# JS7628_base_uart_v1_0.net
KiCad netlist of a schematic drawn in Altium Designer
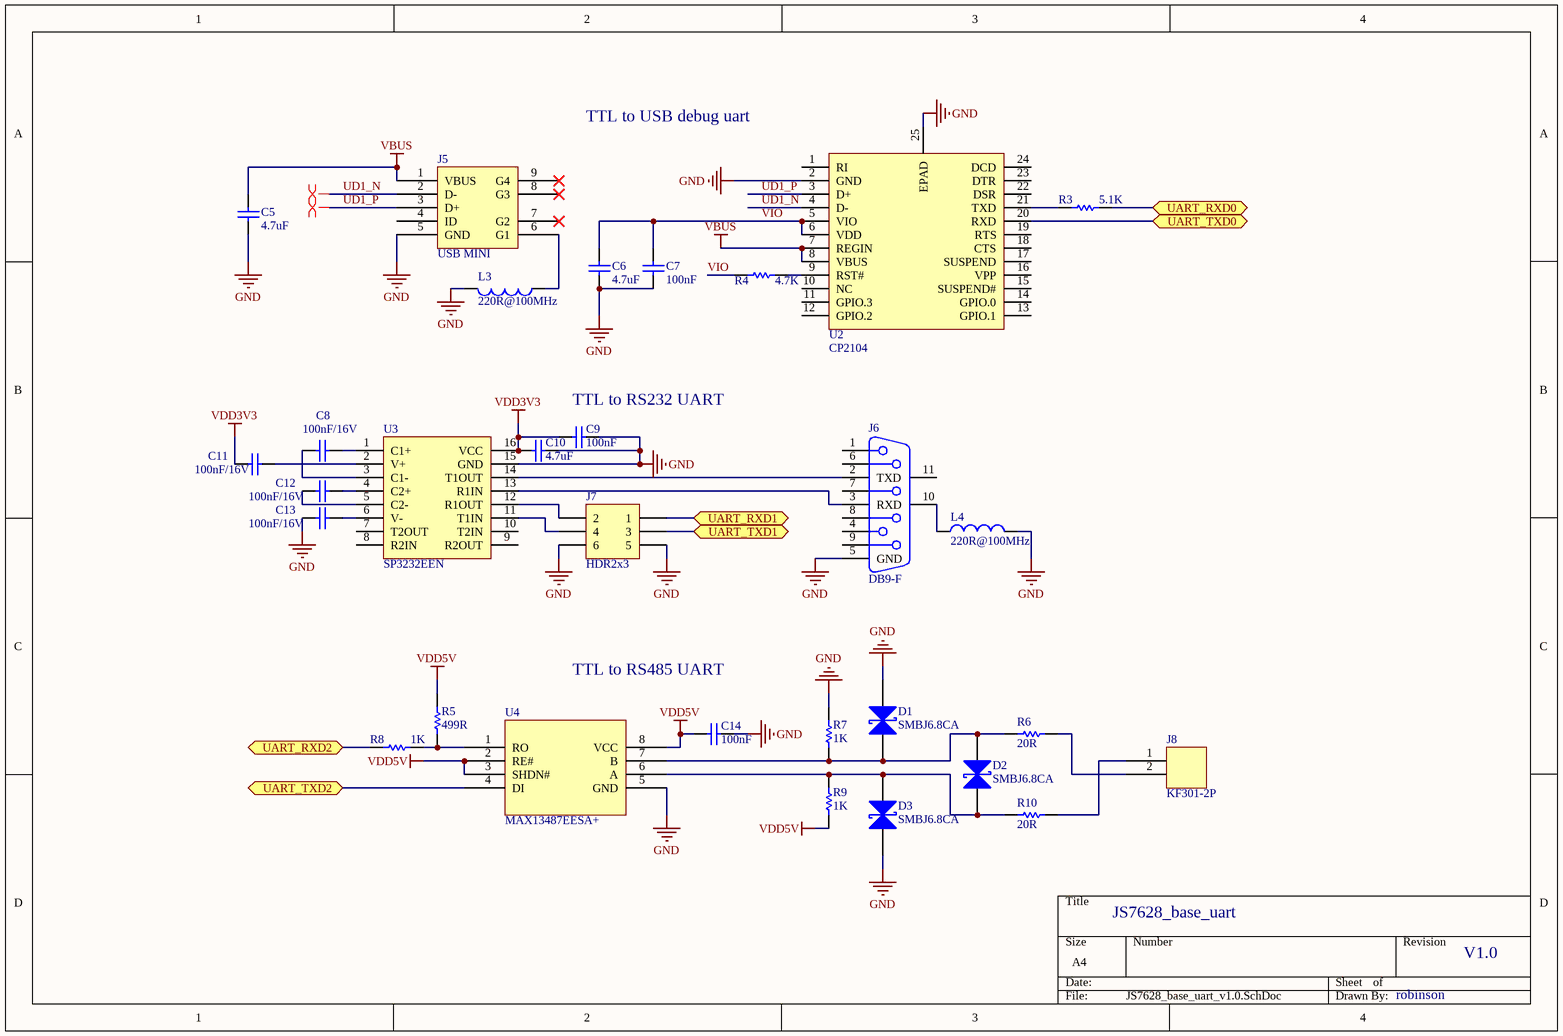
[diagram p0: JS7628_base_uart_v1.0.SchDoc]

(export (version "E")
  (design (tool "Eeschema 10.0.6"))
  (components
    (comp (ref "C5")
      (value "4.7uF")
      (footprint "0603")
      (fields (field (name "Comment") "CAP-SMT"))
      (libsource (lib "MyMiscellaneousDevice") (part "CAP-SMT"))
    )
    (comp (ref "C6")
      (value "4.7uF")
      (footprint "0603")
      (fields (field (name "Comment") "CAP-SMT"))
      (libsource (lib "MyMiscellaneousDevice") (part "CAP-SMT"))
    )
    (comp (ref "C7")
      (value "100nF")
      (footprint "0603")
      (fields (field (name "Comment") "CAP-SMT"))
      (libsource (lib "MyMiscellaneousDevice") (part "CAP-SMT"))
    )
    (comp (ref "C8")
      (value "100nF/16V")
      (footprint "0603")
      (fields (field (name "Comment") "CAP-SMT"))
      (libsource (lib "MyMiscellaneousDevice") (part "CAP-SMT"))
    )
    (comp (ref "C9")
      (value "100nF")
      (footprint "0603")
      (fields (field (name "Comment") "CAP-SMT"))
      (libsource (lib "MyMiscellaneousDevice") (part "CAP-SMT"))
    )
    (comp (ref "C10")
      (value "4.7uF")
      (footprint "0603")
      (fields (field (name "Comment") "CAP-SMT"))
      (libsource (lib "MyMiscellaneousDevice") (part "CAP-SMT"))
    )
    (comp (ref "C11")
      (value "100nF/16V")
      (footprint "0603")
      (fields (field (name "Comment") "CAP-SMT"))
      (libsource (lib "MyMiscellaneousDevice") (part "CAP-SMT"))
    )
    (comp (ref "C12")
      (value "100nF/16V")
      (footprint "0603")
      (fields (field (name "Comment") "CAP-SMT"))
      (libsource (lib "MyMiscellaneousDevice") (part "CAP-SMT"))
    )
    (comp (ref "C13")
      (value "100nF/16V")
      (footprint "0603")
      (fields (field (name "Comment") "CAP-SMT"))
      (libsource (lib "MyMiscellaneousDevice") (part "CAP-SMT"))
    )
    (comp (ref "C14")
      (value "100nF")
      (footprint "0603")
      (fields (field (name "Comment") "CAP-SMT"))
      (libsource (lib "MyMiscellaneousDevice") (part "CAP-SMT"))
    )
    (comp (ref "D1")
      (value "SMBJ6.8CA")
      (footprint "MyMiscellaneousDevice:SMB-BI")
      (libsource (lib "MyMiscellaneousDevice") (part "SMBJ6.8CA"))
    )
    (comp (ref "D2")
      (value "SMBJ6.8CA")
      (footprint "MyMiscellaneousDevice:SMB-BI")
      (libsource (lib "MyMiscellaneousDevice") (part "SMBJ6.8CA"))
    )
    (comp (ref "D3")
      (value "SMBJ6.8CA")
      (footprint "MyMiscellaneousDevice:SMB-BI")
      (libsource (lib "MyMiscellaneousDevice") (part "SMBJ6.8CA"))
    )
    (comp (ref "J5")
      (value "USB MINI")
      (footprint "USB/SM0.8-6H5")
      (libsource (lib "MyMiscellaneousConnector") (part "USB MINI"))
    )
    (comp (ref "J6")
      (value "DB9-F")
      (footprint "DB9-F-90d")
      (libsource (lib "MyMiscellaneousConnector") (part "DB9-F"))
    )
    (comp (ref "J7")
      (value "HDR2x3")
      (footprint "HDR2x3-2.54mm")
      (libsource (lib "MyMiscellaneousConnector") (part "HDR2x3"))
    )
    (comp (ref "J8")
      (value "KF301-2P")
      (footprint "KF301-2P")
      (libsource (lib "MyMiscellaneousConnector") (part "KF301-2P"))
    )
    (comp (ref "L3")
      (value "220R@100MHz")
      (footprint "0603")
      (fields (field (name "Comment") "inductor"))
      (libsource (lib "MyMiscellaneousDevice") (part "inductor"))
    )
    (comp (ref "L4")
      (value "220R@100MHz")
      (footprint "0603")
      (fields (field (name "Comment") "inductor"))
      (libsource (lib "MyMiscellaneousDevice") (part "inductor"))
    )
    (comp (ref "R3")
      (value "5.1K")
      (footprint "0603")
      (fields (field (name "Comment") "RES-SMT"))
      (libsource (lib "MyMiscellaneousDevice") (part "RES-SMT"))
    )
    (comp (ref "R4")
      (value "4.7K")
      (footprint "0603")
      (fields (field (name "Comment") "RES-SMT"))
      (libsource (lib "MyMiscellaneousDevice") (part "RES-SMT"))
    )
    (comp (ref "R5")
      (value "499R")
      (footprint "0603")
      (fields (field (name "Comment") "RES-SMT"))
      (libsource (lib "MyMiscellaneousDevice") (part "RES-SMT"))
    )
    (comp (ref "R6")
      (value "20R")
      (footprint "0805")
      (fields (field (name "Comment") "RES-SMT"))
      (libsource (lib "MyMiscellaneousDevice") (part "RES-SMT"))
    )
    (comp (ref "R7")
      (value "1K")
      (footprint "0603")
      (fields (field (name "Comment") "RES-SMT"))
      (libsource (lib "MyMiscellaneousDevice") (part "RES-SMT"))
    )
    (comp (ref "R8")
      (value "1K")
      (footprint "0603")
      (fields (field (name "Comment") "RES-SMT"))
      (libsource (lib "MyMiscellaneousDevice") (part "RES-SMT"))
    )
    (comp (ref "R9")
      (value "1K")
      (footprint "0603")
      (fields (field (name "Comment") "RES-SMT"))
      (libsource (lib "MyMiscellaneousDevice") (part "RES-SMT"))
    )
    (comp (ref "R10")
      (value "20R")
      (footprint "0805")
      (fields (field (name "Comment") "RES-SMT"))
      (libsource (lib "MyMiscellaneousDevice") (part "RES-SMT"))
    )
    (comp (ref "U2")
      (value "CP2104")
      (footprint "MyMiscellaneousDevice:QFN-24")
      (libsource (lib "MyMiscellaneousDevice") (part "CP2104"))
    )
    (comp (ref "U3")
      (value "SP3232EEN")
      (footprint "SOIC16_N")
      (libsource (lib "MyMiscellaneousDevice") (part "SP3232EEN"))
    )
    (comp (ref "U4")
      (value "MAX13487EESA+")
      (footprint "MyMiscellaneousDevice:SOIC-8P")
      (libsource (lib "MyMiscellaneousDevice") (part "MAX13487EESA+"))
    )
  )
  (nets
    (net (code "1") (name "/UART_RXD0") (class "Default")
      (node (ref "R3") (pin "2") (pinfunction "2_2") (pintype "passive"))
    )
    (net (code "2") (name "/UART_RXD1") (class "Default")
      (node (ref "J7") (pin "1") (pinfunction "1_1") (pintype "passive"))
    )
    (net (code "3") (name "/UART_RXD2") (class "Default")
      (node (ref "R8") (pin "1") (pinfunction "1_1") (pintype "passive"))
    )
    (net (code "4") (name "/UART_TXD0") (class "Default")
      (node (ref "U2") (pin "20") (pinfunction "RXD_20") (pintype "passive"))
    )
    (net (code "5") (name "/UART_TXD1") (class "Default")
      (node (ref "J7") (pin "3") (pinfunction "3_3") (pintype "passive"))
    )
    (net (code "6") (name "/UART_TXD2") (class "Default")
      (node (ref "U4") (pin "4") (pinfunction "DI_4") (pintype "passive"))
    )
    (net (code "7") (name "/UD1_N") (class "Default")
      (node (ref "J5") (pin "2") (pinfunction "D-_2") (pintype "passive"))
      (node (ref "U2") (pin "4") (pinfunction "D-_4") (pintype "passive"))
    )
    (net (code "8") (name "/UD1_P") (class "Default")
      (node (ref "J5") (pin "3") (pinfunction "D+_3") (pintype "passive"))
      (node (ref "U2") (pin "3") (pinfunction "D+_3") (pintype "passive"))
    )
    (net (code "9") (name "/VIO") (class "Default")
      (node (ref "C6") (pin "2") (pinfunction "2_2") (pintype "passive"))
      (node (ref "C7") (pin "2") (pinfunction "2_2") (pintype "passive"))
      (node (ref "R4") (pin "1") (pinfunction "1_1") (pintype "passive"))
      (node (ref "U2") (pin "5") (pinfunction "VIO_5") (pintype "passive"))
      (node (ref "U2") (pin "6") (pinfunction "VDD_6") (pintype "passive"))
    )
    (net (code "10") (name "GND") (class "Default")
      (node (ref "C10") (pin "2") (pinfunction "2_2") (pintype "passive"))
      (node (ref "C13") (pin "2") (pinfunction "2_2") (pintype "passive"))
      (node (ref "C14") (pin "2") (pinfunction "2_2") (pintype "passive"))
      (node (ref "C5") (pin "1") (pinfunction "1_1") (pintype "passive"))
      (node (ref "C6") (pin "1") (pinfunction "1_1") (pintype "passive"))
      (node (ref "C7") (pin "1") (pinfunction "1_1") (pintype "passive"))
      (node (ref "C9") (pin "2") (pinfunction "2_2") (pintype "passive"))
      (node (ref "D1") (pin "2") (pinfunction "K_2") (pintype "passive"))
      (node (ref "D3") (pin "1") (pinfunction "A_1") (pintype "passive"))
      (node (ref "J5") (pin "5") (pinfunction "GND_5") (pintype "passive"))
      (node (ref "J6") (pin "5") (pinfunction "GND_5") (pintype "passive"))
      (node (ref "J7") (pin "5") (pinfunction "5_5") (pintype "passive"))
      (node (ref "J7") (pin "6") (pinfunction "6_6") (pintype "passive"))
      (node (ref "L3") (pin "2") (pinfunction "2_2") (pintype "passive"))
      (node (ref "L4") (pin "2") (pinfunction "2_2") (pintype "passive"))
      (node (ref "R7") (pin "1") (pinfunction "1_1") (pintype "passive"))
      (node (ref "U2") (pin "2") (pinfunction "GND_2") (pintype "passive"))
      (node (ref "U2") (pin "25") (pinfunction "EPAD_25") (pintype "passive"))
      (node (ref "U3") (pin "15") (pinfunction "GND_15") (pintype "passive"))
      (node (ref "U4") (pin "5") (pinfunction "GND_5") (pintype "passive"))
    )
    (net (code "11") (name "Net-(D1-A)") (class "Default")
      (node (ref "D1") (pin "1") (pinfunction "A_1") (pintype "passive"))
      (node (ref "D2") (pin "2") (pinfunction "K_2") (pintype "passive"))
      (node (ref "R6") (pin "1") (pinfunction "1_1") (pintype "passive"))
      (node (ref "R7") (pin "2") (pinfunction "2_2") (pintype "passive"))
      (node (ref "U4") (pin "7") (pinfunction "B_7") (pintype "passive"))
    )
    (net (code "12") (name "Net-(D2-A)") (class "Default")
      (node (ref "D2") (pin "1") (pinfunction "A_1") (pintype "passive"))
      (node (ref "D3") (pin "2") (pinfunction "K_2") (pintype "passive"))
      (node (ref "R10") (pin "1") (pinfunction "1_1") (pintype "passive"))
      (node (ref "R9") (pin "1") (pinfunction "1_1") (pintype "passive"))
      (node (ref "U4") (pin "6") (pinfunction "A_6") (pintype "passive"))
    )
    (net (code "13") (name "Net-(J5-G1)") (class "Default")
      (node (ref "J5") (pin "6") (pinfunction "G1_6") (pintype "passive"))
      (node (ref "L3") (pin "1") (pinfunction "1_1") (pintype "passive"))
    )
    (net (code "14") (name "Net-(J6-MH1)") (class "Default")
      (node (ref "J6") (pin "10") (pinfunction "MH1_10") (pintype "passive"))
      (node (ref "L4") (pin "1") (pinfunction "1_1") (pintype "passive"))
    )
    (net (code "15") (name "Net-(J6-RXD)") (class "Default")
      (node (ref "J6") (pin "3") (pinfunction "RXD_3") (pintype "passive"))
      (node (ref "U3") (pin "13") (pinfunction "R1IN_13") (pintype "passive"))
    )
    (net (code "16") (name "Net-(J6-TXD)") (class "Default")
      (node (ref "J6") (pin "2") (pinfunction "TXD_2") (pintype "passive"))
      (node (ref "U3") (pin "14") (pinfunction "T1OUT_14") (pintype "passive"))
    )
    (net (code "17") (name "Net-(J8-Pad1)") (class "Default")
      (node (ref "J8") (pin "1") (pinfunction "1_1") (pintype "passive"))
      (node (ref "R10") (pin "2") (pinfunction "2_2") (pintype "passive"))
    )
    (net (code "18") (name "Net-(J8-Pad2)") (class "Default")
      (node (ref "J8") (pin "2") (pinfunction "2_2") (pintype "passive"))
      (node (ref "R6") (pin "2") (pinfunction "2_2") (pintype "passive"))
    )
    (net (code "19") (name "Net-(U2-RST#)") (class "Default")
      (node (ref "R4") (pin "2") (pinfunction "2_2") (pintype "passive"))
      (node (ref "U2") (pin "9") (pinfunction "RST#_9") (pintype "passive"))
    )
    (net (code "20") (name "Net-(U2-TXD)") (class "Default")
      (node (ref "R3") (pin "1") (pinfunction "1_1") (pintype "passive"))
      (node (ref "U2") (pin "21") (pinfunction "TXD_21") (pintype "passive"))
    )
    (net (code "21") (name "Net-(U3-C1+)") (class "Default")
      (node (ref "C8") (pin "1") (pinfunction "1_1") (pintype "passive"))
      (node (ref "U3") (pin "1") (pinfunction "C1+_1") (pintype "passive"))
    )
    (net (code "22") (name "Net-(U3-C1-)") (class "Default")
      (node (ref "C8") (pin "2") (pinfunction "2_2") (pintype "passive"))
      (node (ref "U3") (pin "3") (pinfunction "C1-_3") (pintype "passive"))
    )
    (net (code "23") (name "Net-(U3-C2+)") (class "Default")
      (node (ref "C12") (pin "1") (pinfunction "1_1") (pintype "passive"))
      (node (ref "U3") (pin "4") (pinfunction "C2+_4") (pintype "passive"))
    )
    (net (code "24") (name "Net-(U3-C2-)") (class "Default")
      (node (ref "C12") (pin "2") (pinfunction "2_2") (pintype "passive"))
      (node (ref "U3") (pin "5") (pinfunction "C2-_5") (pintype "passive"))
    )
    (net (code "25") (name "Net-(U3-R1OUT)") (class "Default")
      (node (ref "J7") (pin "2") (pinfunction "2_2") (pintype "passive"))
      (node (ref "U3") (pin "12") (pinfunction "R1OUT_12") (pintype "passive"))
    )
    (net (code "26") (name "Net-(U3-T1IN)") (class "Default")
      (node (ref "J7") (pin "4") (pinfunction "4_4") (pintype "passive"))
      (node (ref "U3") (pin "11") (pinfunction "T1IN_11") (pintype "passive"))
    )
    (net (code "27") (name "Net-(U3-V+)") (class "Default")
      (node (ref "C11") (pin "1") (pinfunction "1_1") (pintype "passive"))
      (node (ref "U3") (pin "2") (pinfunction "V+_2") (pintype "passive"))
    )
    (net (code "28") (name "Net-(U3-V-)") (class "Default")
      (node (ref "C13") (pin "1") (pinfunction "1_1") (pintype "passive"))
      (node (ref "U3") (pin "6") (pinfunction "V-_6") (pintype "passive"))
    )
    (net (code "29") (name "Net-(U4-RO)") (class "Default")
      (node (ref "R5") (pin "2") (pinfunction "2_2") (pintype "passive"))
      (node (ref "R8") (pin "2") (pinfunction "2_2") (pintype "passive"))
      (node (ref "U4") (pin "1") (pinfunction "RO_1") (pintype "passive"))
    )
    (net (code "30") (name "VBUS") (class "Default")
      (node (ref "C5") (pin "2") (pinfunction "2_2") (pintype "passive"))
      (node (ref "J5") (pin "1") (pinfunction "VBUS_1") (pintype "passive"))
      (node (ref "U2") (pin "7") (pinfunction "REGIN_7") (pintype "passive"))
      (node (ref "U2") (pin "8") (pinfunction "VBUS_8") (pintype "passive"))
    )
    (net (code "31") (name "VDD3V3") (class "Default")
      (node (ref "C10") (pin "1") (pinfunction "1_1") (pintype "passive"))
      (node (ref "C11") (pin "2") (pinfunction "2_2") (pintype "passive"))
      (node (ref "C9") (pin "1") (pinfunction "1_1") (pintype "passive"))
      (node (ref "U3") (pin "16") (pinfunction "VCC_16") (pintype "passive"))
    )
    (net (code "32") (name "VDD5V") (class "Default")
      (node (ref "C14") (pin "1") (pinfunction "1_1") (pintype "passive"))
      (node (ref "R5") (pin "1") (pinfunction "1_1") (pintype "passive"))
      (node (ref "R9") (pin "2") (pinfunction "2_2") (pintype "passive"))
      (node (ref "U4") (pin "2") (pinfunction "RE#_2") (pintype "passive"))
      (node (ref "U4") (pin "3") (pinfunction "SHDN#_3") (pintype "passive"))
      (node (ref "U4") (pin "8") (pinfunction "VCC_8") (pintype "passive"))
    )
    (net (code "33") (name "unconnected-(J5-G2-Pad7)") (class "Default")
      (node (ref "J5") (pin "7") (pinfunction "G2_7") (pintype "passive+no_connect"))
    )
    (net (code "34") (name "unconnected-(J5-G3-Pad8)") (class "Default")
      (node (ref "J5") (pin "8") (pinfunction "G3_8") (pintype "passive+no_connect"))
    )
    (net (code "35") (name "unconnected-(J5-G4-Pad9)") (class "Default")
      (node (ref "J5") (pin "9") (pinfunction "G4_9") (pintype "passive+no_connect"))
    )
    (net (code "36") (name "unconnected-(J5-ID-Pad4)") (class "Default")
      (node (ref "J5") (pin "4") (pinfunction "ID_4") (pintype "passive"))
    )
    (net (code "37") (name "unconnected-(J6-MH2-Pad11)") (class "Default")
      (node (ref "J6") (pin "11") (pinfunction "MH2_11") (pintype "passive"))
    )
    (net (code "38") (name "unconnected-(J6-Pad1)") (class "Default")
      (node (ref "J6") (pin "1") (pinfunction "1_1") (pintype "passive"))
    )
    (net (code "39") (name "unconnected-(J6-Pad4)") (class "Default")
      (node (ref "J6") (pin "4") (pinfunction "4_4") (pintype "passive"))
    )
    (net (code "40") (name "unconnected-(J6-Pad6)") (class "Default")
      (node (ref "J6") (pin "6") (pinfunction "6_6") (pintype "passive"))
    )
    (net (code "41") (name "unconnected-(J6-Pad7)") (class "Default")
      (node (ref "J6") (pin "7") (pinfunction "7_7") (pintype "passive"))
    )
    (net (code "42") (name "unconnected-(J6-Pad8)") (class "Default")
      (node (ref "J6") (pin "8") (pinfunction "8_8") (pintype "passive"))
    )
    (net (code "43") (name "unconnected-(J6-Pad9)") (class "Default")
      (node (ref "J6") (pin "9") (pinfunction "9_9") (pintype "passive"))
    )
    (net (code "44") (name "unconnected-(U2-CTS-Pad18)") (class "Default")
      (node (ref "U2") (pin "18") (pinfunction "CTS_18") (pintype "passive"))
    )
    (net (code "45") (name "unconnected-(U2-DCD-Pad24)") (class "Default")
      (node (ref "U2") (pin "24") (pinfunction "DCD_24") (pintype "passive"))
    )
    (net (code "46") (name "unconnected-(U2-DSR-Pad22)") (class "Default")
      (node (ref "U2") (pin "22") (pinfunction "DSR_22") (pintype "passive"))
    )
    (net (code "47") (name "unconnected-(U2-DTR-Pad23)") (class "Default")
      (node (ref "U2") (pin "23") (pinfunction "DTR_23") (pintype "passive"))
    )
    (net (code "48") (name "unconnected-(U2-GPIO.0-Pad14)") (class "Default")
      (node (ref "U2") (pin "14") (pinfunction "GPIO.0_14") (pintype "passive"))
    )
    (net (code "49") (name "unconnected-(U2-GPIO.1-Pad13)") (class "Default")
      (node (ref "U2") (pin "13") (pinfunction "GPIO.1_13") (pintype "passive"))
    )
    (net (code "50") (name "unconnected-(U2-GPIO.2-Pad12)") (class "Default")
      (node (ref "U2") (pin "12") (pinfunction "GPIO.2_12") (pintype "passive"))
    )
    (net (code "51") (name "unconnected-(U2-GPIO.3-Pad11)") (class "Default")
      (node (ref "U2") (pin "11") (pinfunction "GPIO.3_11") (pintype "passive"))
    )
    (net (code "52") (name "unconnected-(U2-NC-Pad10)") (class "Default")
      (node (ref "U2") (pin "10") (pinfunction "NC_10") (pintype "passive"))
    )
    (net (code "53") (name "unconnected-(U2-RI-Pad1)") (class "Default")
      (node (ref "U2") (pin "1") (pinfunction "RI_1") (pintype "passive"))
    )
    (net (code "54") (name "unconnected-(U2-RTS-Pad19)") (class "Default")
      (node (ref "U2") (pin "19") (pinfunction "RTS_19") (pintype "passive"))
    )
    (net (code "55") (name "unconnected-(U2-SUSPEND#-Pad15)") (class "Default")
      (node (ref "U2") (pin "15") (pinfunction "SUSPEND#_15") (pintype "passive"))
    )
    (net (code "56") (name "unconnected-(U2-SUSPEND-Pad17)") (class "Default")
      (node (ref "U2") (pin "17") (pinfunction "SUSPEND_17") (pintype "passive"))
    )
    (net (code "57") (name "unconnected-(U2-VPP-Pad16)") (class "Default")
      (node (ref "U2") (pin "16") (pinfunction "VPP_16") (pintype "passive"))
    )
    (net (code "58") (name "unconnected-(U3-R2IN-Pad8)") (class "Default")
      (node (ref "U3") (pin "8") (pinfunction "R2IN_8") (pintype "passive"))
    )
    (net (code "59") (name "unconnected-(U3-R2OUT-Pad9)") (class "Default")
      (node (ref "U3") (pin "9") (pinfunction "R2OUT_9") (pintype "passive"))
    )
    (net (code "60") (name "unconnected-(U3-T2IN-Pad10)") (class "Default")
      (node (ref "U3") (pin "10") (pinfunction "T2IN_10") (pintype "passive"))
    )
    (net (code "61") (name "unconnected-(U3-T2OUT-Pad7)") (class "Default")
      (node (ref "U3") (pin "7") (pinfunction "T2OUT_7") (pintype "passive"))
    )
  )
)
